# Isolator.net
KiCad netlist of a schematic drawn in Altium Designer
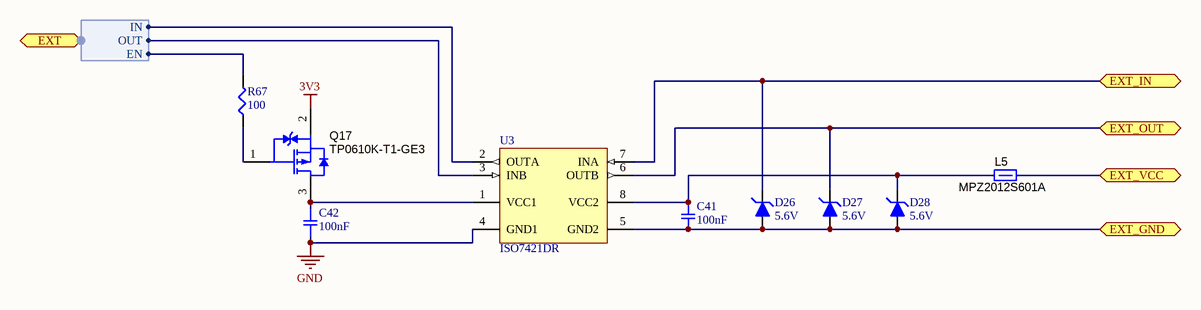
[diagram p0: Isolator.SchDoc]

(export (version "E")
  (design (tool "Eeschema 10.0.6"))
  (components
    (comp (ref "C41")
      (value "100nF")
      (footprint "SMD-0603C")
      (description "CAP CER 0.1UF 16V X7R 0603")
      (fields
        (field (name "DIGI-KEY PART NUMBER") "490-5796-1-ND")
        (field (name "PART NUMBER") "GCJ188R71C104KA01D")
      )
      (libsource (lib "capacitor_murata_0603") (part "GCJ188R71C104KA01D"))
    )
    (comp (ref "C42")
      (value "100nF")
      (footprint "SMD-0603C")
      (description "CAP CER 0.1UF 16V X7R 0603")
      (fields
        (field (name "DIGI-KEY PART NUMBER") "490-5796-1-ND")
        (field (name "PART NUMBER") "GCJ188R71C104KA01D")
      )
      (libsource (lib "capacitor_murata_0603") (part "GCJ188R71C104KA01D"))
    )
    (comp (ref "D26")
      (value "5.6V")
      (footprint "SOD-323")
      (description "Zener Diode 5.6V")
      (libsource (lib "Components") (part "ZENER_5V6"))
    )
    (comp (ref "D27")
      (value "5.6V")
      (footprint "SOD-323")
      (description "Zener Diode 5.6V")
      (libsource (lib "Components") (part "ZENER_5V6"))
    )
    (comp (ref "D28")
      (value "5.6V")
      (footprint "SOD-323")
      (description "Zener Diode 5.6V")
      (libsource (lib "Components") (part "ZENER_5V6"))
    )
    (comp (ref "L5")
      (value "MPZ2012S601A")
      (footprint "SMD-0805-RES")
      (description "Ferrite Bead")
      (fields
        (field (name "PARTNUMBER") "BLM18SG221TN1D")
        (field (name "MANUFACTURER") "MuRata")
        (field (name "PUBLISHER") "Texas Instruments")
      )
      (libsource (lib "Components") (part "BLM18SG221TN1D"))
    )
    (comp (ref "Q17")
      (value "TP0610K-T1-GE3")
      (footprint "SOT23-3")
      (description "MOSFET, P-CH, -60 V, -0.185 A, SOT-23")
      (fields
        (field (name "MANUFACTURER") "Vishay-Siliconix")
        (field (name "SYMBOLCREATOR") "a0411947")
        (field (name "PUBLISHER") "Texas Instruments")
      )
      (libsource (lib "Components") (part "TP0610K-T1-GE3"))
    )
    (comp (ref "R67")
      (value "100")
      (footprint "SMD-0603-RES")
      (description "RES SMD 100 OHM 1% 1/10W 0603")
      (fields (field (name "PART NUMBER") "ERJ-3EKF1000V") (field (name "DIGI-KEY PART NUMBER") "P100HCT-ND"))
      (libsource (lib "Panasonic_ERJ_0603") (part "ERJ-3EKF1000V"))
    )
    (comp (ref "U3")
      (value "ISO7421DR")
      (footprint "D0008A_N")
      (fields (field (name "MANUFACTURER") "Texas Instruments"))
      (libsource (lib "TI Interface Isolator") (part "ISO7421DR"))
    )
  )
  (nets
    (net (code "2") (name "/EN") (class "Default")
      (node (ref "R67") (pin "2") (pinfunction "2_2") (pintype "passive"))
    )
    (net (code "3") (name "/EXT_GND") (class "Default")
      (node (ref "C41") (pin "2") (pinfunction "2_2") (pintype "passive"))
      (node (ref "D26") (pin "2") (pinfunction "A_2") (pintype "passive"))
      (node (ref "D27") (pin "2") (pinfunction "A_2") (pintype "passive"))
      (node (ref "D28") (pin "2") (pinfunction "A_2") (pintype "passive"))
      (node (ref "U3") (pin "5") (pinfunction "GND2_5") (pintype "power_in"))
    )
    (net (code "4") (name "/EXT_IN") (class "Default")
      (node (ref "D26") (pin "1") (pinfunction "K_1") (pintype "passive"))
      (node (ref "U3") (pin "7") (pinfunction "INA_7") (pintype "input"))
    )
    (net (code "5") (name "/EXT_OUT") (class "Default")
      (node (ref "D27") (pin "1") (pinfunction "K_1") (pintype "passive"))
      (node (ref "U3") (pin "6") (pinfunction "OUTB_6") (pintype "output"))
    )
    (net (code "6") (name "/EXT_VCC") (class "Default")
      (node (ref "L5") (pin "1") (pinfunction "1_1") (pintype "passive"))
    )
    (net (code "7") (name "/IN") (class "Default")
      (node (ref "U3") (pin "2") (pinfunction "OUTA_2") (pintype "output"))
    )
    (net (code "8") (name "/OUT") (class "Default")
      (node (ref "U3") (pin "3") (pinfunction "INB_3") (pintype "input"))
    )
    (net (code "10") (name "3V3") (class "Default")
      (node (ref "Q17") (pin "2") (pinfunction "S_2") (pintype "passive"))
    )
    (net (code "11") (name "GND") (class "Default")
      (node (ref "C42") (pin "2") (pinfunction "2_2") (pintype "passive"))
      (node (ref "U3") (pin "4") (pinfunction "GND1_4") (pintype "power_in"))
    )
    (net (code "12") (name "Net-(D28-K)") (class "Default")
      (node (ref "C41") (pin "1") (pinfunction "1_1") (pintype "passive"))
      (node (ref "D28") (pin "1") (pinfunction "K_1") (pintype "passive"))
      (node (ref "L5") (pin "2") (pinfunction "2_2") (pintype "passive"))
      (node (ref "U3") (pin "8") (pinfunction "VCC2_8") (pintype "power_in"))
    )
    (net (code "13") (name "Net-(Q17-D)") (class "Default")
      (node (ref "C42") (pin "1") (pinfunction "1_1") (pintype "passive"))
      (node (ref "Q17") (pin "3") (pinfunction "D_3") (pintype "passive"))
      (node (ref "U3") (pin "1") (pinfunction "VCC1_1") (pintype "power_in"))
    )
    (net (code "14") (name "Net-(Q17-G)") (class "Default")
      (node (ref "Q17") (pin "1") (pinfunction "G_1") (pintype "passive"))
      (node (ref "R67") (pin "1") (pinfunction "1_1") (pintype "passive"))
    )
  )
)
